# keyless-esp32.net
KiCad netlist of a schematic drawn in EAGLE
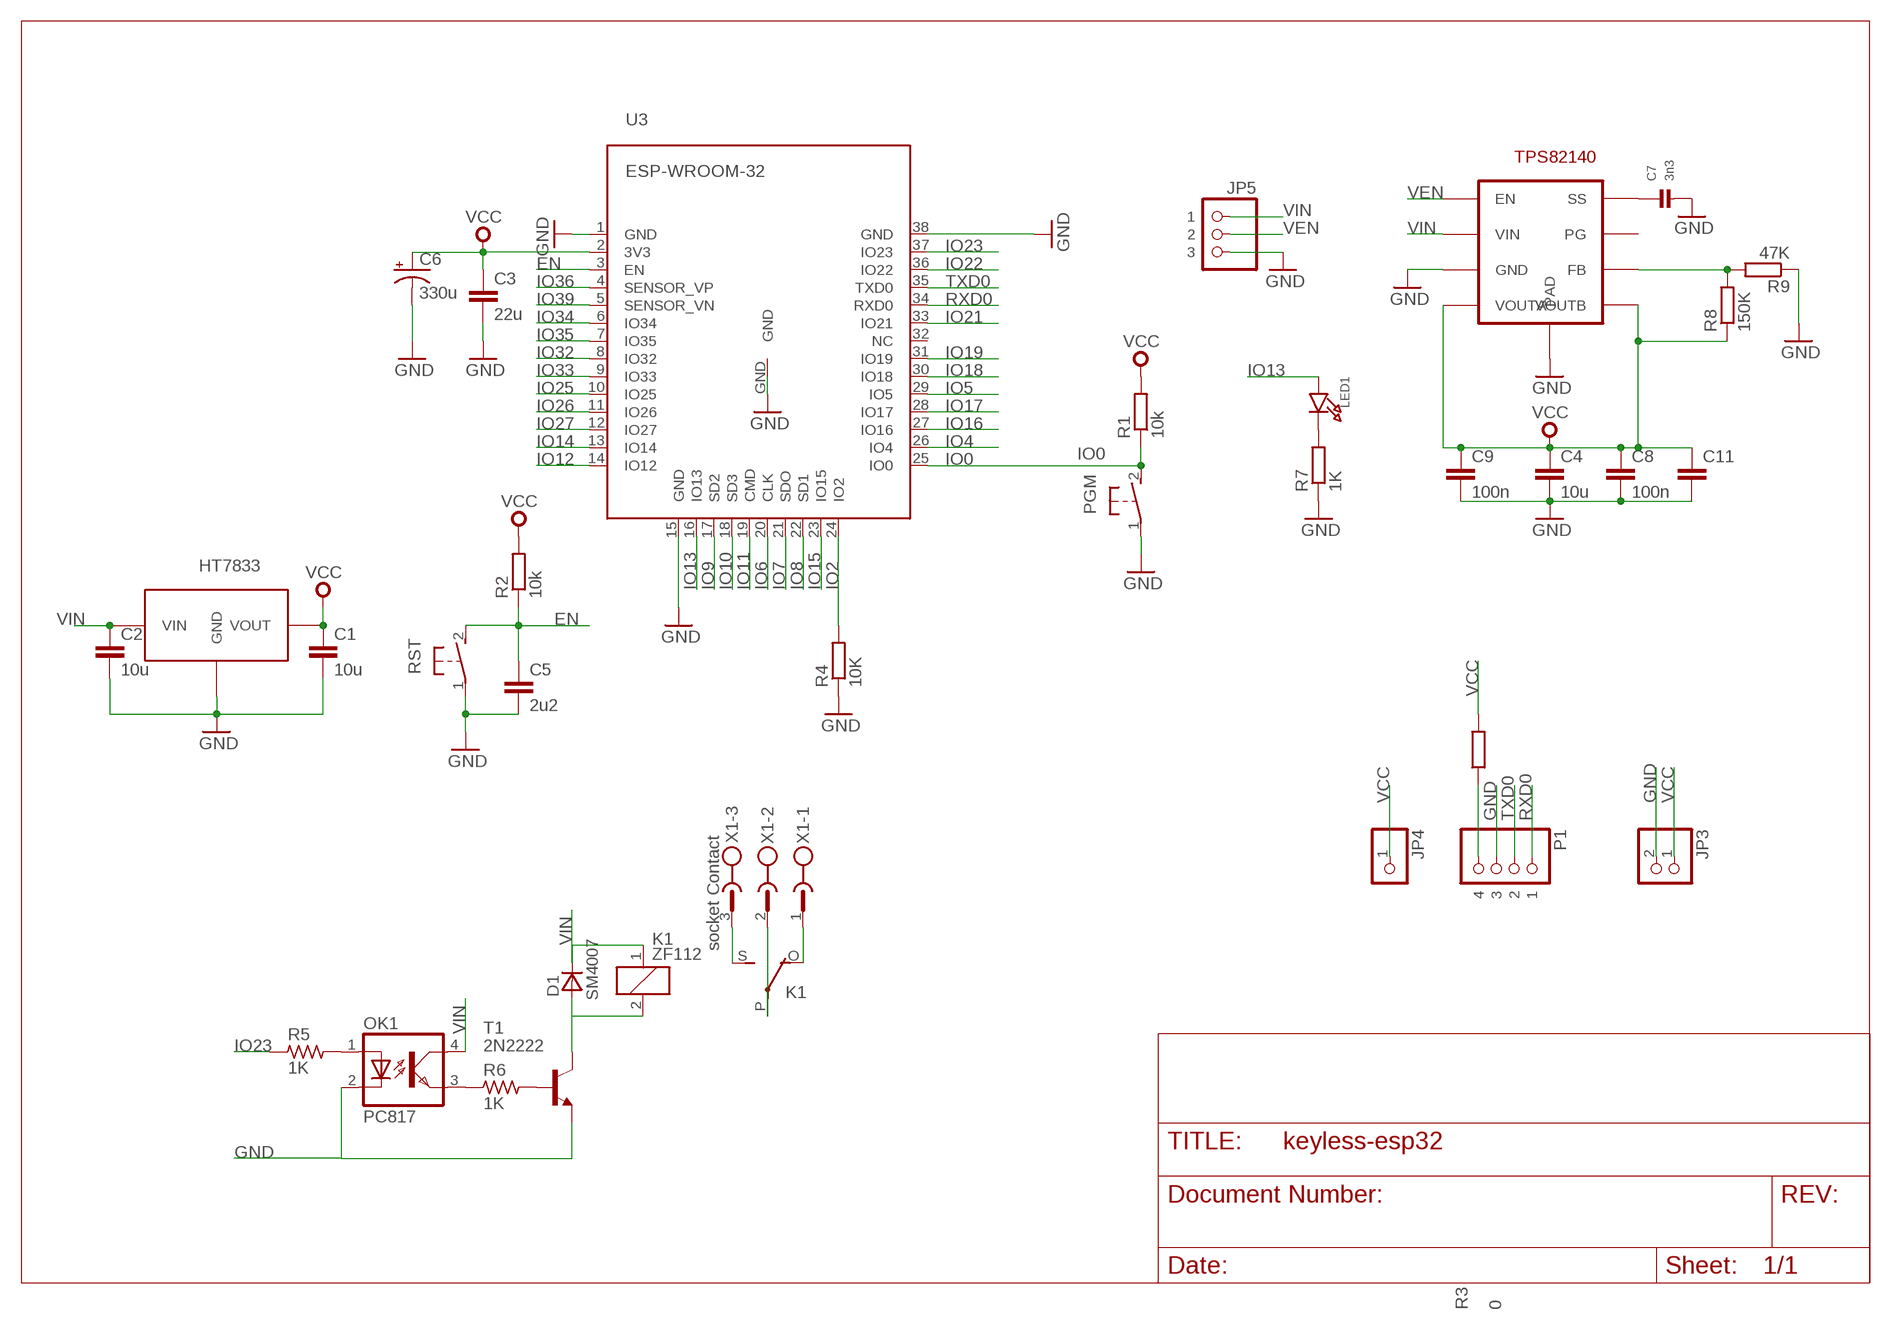
[diagram p0: schematic, sheet 1]

(export (version "E")
  (design (tool "Eeschema 10.0.6"))
  (components
    (comp (ref "C1")
      (value "10u")
      (footprint "eagle-import:C0603")
      (libsource (lib "eagle-import") (part "C-EUC0603"))
    )
    (comp (ref "C2")
      (value "10u")
      (footprint "eagle-import:C0603")
      (libsource (lib "eagle-import") (part "C-EUC0603"))
    )
    (comp (ref "C3")
      (value "22u")
      (footprint "eagle-import:0805")
      (libsource (lib "eagle-import") (part "CAP0805"))
    )
    (comp (ref "C4")
      (value "10u")
      (footprint "eagle-import:C0603")
      (libsource (lib "eagle-import") (part "C-EUC0603"))
    )
    (comp (ref "C5")
      (value "2u2")
      (footprint "eagle-import:C0603")
      (libsource (lib "eagle-import") (part "C-EUC0603"))
    )
    (comp (ref "C6")
      (value "330u")
      (footprint "eagle-import:VISHAY_C")
      (libsource (lib "eagle-import") (part "CAP_POLSMD"))
    )
    (comp (ref "C7")
      (value "3n3")
      (footprint "eagle-import:0603")
      (libsource (lib "eagle-import") (part "CAP_CERAMIC0603"))
    )
    (comp (ref "C8")
      (value "100n")
      (footprint "eagle-import:C0603")
      (libsource (lib "eagle-import") (part "C-EUC0603"))
    )
    (comp (ref "C9")
      (value "100n")
      (footprint "eagle-import:C0603")
      (libsource (lib "eagle-import") (part "C-EUC0603"))
    )
    (comp (ref "C11")
      (value "CAPSMD")
      (footprint "eagle-import:GRM43D")
      (libsource (lib "eagle-import") (part "CAPSMD"))
    )
    (comp (ref "D1")
      (value "SM4007")
      (footprint "eagle-import:MELF-MLL41")
      (libsource (lib "eagle-import") (part "SM4007"))
    )
    (comp (ref "JP3")
      (value "HEADER-1X2ROUND")
      (footprint "eagle-import:1X02_ROUND")
      (libsource (lib "eagle-import") (part "HEADER-1X2ROUND"))
    )
    (comp (ref "JP4")
      (value "HEADER-1X1ROUND")
      (footprint "eagle-import:1X01_ROUND")
      (libsource (lib "eagle-import") (part "HEADER-1X1ROUND"))
    )
    (comp (ref "JP5")
      (value "HEADER-1X3ROUND")
      (footprint "eagle-import:1X03_ROUND")
      (libsource (lib "eagle-import") (part "HEADER-1X3ROUND"))
    )
    (comp (ref "K1")
      (value "ZF112")
      (footprint "eagle-import:ZF112")
      (libsource (lib "eagle-import") (part "ZF112"))
    )
    (comp (ref "LED1")
      (value "LED0603")
      (footprint "eagle-import:CHIPLED_0603")
      (libsource (lib "eagle-import") (part "LED0603"))
    )
    (comp (ref "OK1")
      (value "PC817")
      (footprint "eagle-import:DIL04")
      (fields (field (name "MPN") "PC817X4J000F"))
      (libsource (lib "eagle-import") (part "PC817"))
    )
    (comp (ref "P1")
      (value "HEADER-1X4ROUND")
      (footprint "eagle-import:1X04_ROUND")
      (libsource (lib "eagle-import") (part "HEADER-1X4ROUND"))
    )
    (comp (ref "PGM")
      (value "DTSM-3")
      (footprint "eagle-import:DTSM-3")
      (libsource (lib "eagle-import") (part "DTSM-3"))
    )
    (comp (ref "R1")
      (value "10k")
      (footprint "eagle-import:R0603")
      (libsource (lib "eagle-import") (part "R-EU_R0603"))
    )
    (comp (ref "R2")
      (value "10k")
      (footprint "eagle-import:R0603")
      (libsource (lib "eagle-import") (part "R-EU_R0603"))
    )
    (comp (ref "R3")
      (value "0")
      (footprint "eagle-import:R0603")
      (libsource (lib "eagle-import") (part "R-EU_R0603"))
    )
    (comp (ref "R4")
      (value "10K")
      (footprint "eagle-import:R0603")
      (libsource (lib "eagle-import") (part "R-EU_R0603"))
    )
    (comp (ref "R5")
      (value "1K")
      (footprint "eagle-import:R0805")
      (libsource (lib "eagle-import") (part "R_0805"))
    )
    (comp (ref "R6")
      (value "1K")
      (footprint "eagle-import:R0805")
      (libsource (lib "eagle-import") (part "R_0805"))
    )
    (comp (ref "R7")
      (value "1K")
      (footprint "eagle-import:R0603")
      (libsource (lib "eagle-import") (part "R-EU_R0603"))
    )
    (comp (ref "R8")
      (value "150K")
      (footprint "eagle-import:R0603")
      (libsource (lib "eagle-import") (part "R-EU_R0603"))
    )
    (comp (ref "R9")
      (value "47K")
      (footprint "eagle-import:R0603")
      (libsource (lib "eagle-import") (part "R-EU_R0603"))
    )
    (comp (ref "RST")
      (value "DTSM-3")
      (footprint "eagle-import:DTSM-3")
      (libsource (lib "eagle-import") (part "DTSM-3"))
    )
    (comp (ref "T1")
      (value "2N2222")
      (footprint "eagle-import:TO18")
      (libsource (lib "eagle-import") (part "2N2222"))
    )
    (comp (ref "U$1")
      (value "HT7833")
      (footprint "eagle-import:SOT89")
      (libsource (lib "eagle-import") (part "HT7333"))
    )
    (comp (ref "U$2")
      (value "TPS82140")
      (footprint "eagle-import:TPS82140")
      (libsource (lib "eagle-import") (part "TPS82140"))
    )
    (comp (ref "U3")
      (value "ESP-WROOM-32")
      (footprint "eagle-import:ESP-WROOM-32")
      (libsource (lib "eagle-import") (part "ESP-WROOM-32"))
    )
    (comp (ref "X1")
      (value "socket Contact")
      (footprint "eagle-import:W232-3")
      (libsource (lib "eagle-import") (part "W232-3"))
    )
  )
  (nets
    (net (code "1") (name "/EN") (class "Default")
      (node (ref "C5") (pin "1") (pinfunction "1_1") (pintype "passive"))
      (node (ref "R2") (pin "1") (pinfunction "1_1") (pintype "passive"))
      (node (ref "RST") (pin "2") (pinfunction "2_2") (pintype "passive"))
      (node (ref "U3") (pin "3") (pinfunction "EN_3") (pintype "bidirectional"))
    )
    (net (code "2") (name "/IO0") (class "Default")
      (node (ref "PGM") (pin "2") (pinfunction "2_2") (pintype "passive"))
      (node (ref "R1") (pin "1") (pinfunction "1_1") (pintype "passive"))
      (node (ref "U3") (pin "25") (pinfunction "IO0_25") (pintype "bidirectional"))
    )
    (net (code "3") (name "/IO2") (class "Default")
      (node (ref "R4") (pin "2") (pinfunction "2_2") (pintype "passive"))
      (node (ref "U3") (pin "24") (pinfunction "IO2_24") (pintype "bidirectional"))
    )
    (net (code "4") (name "/IO4") (class "Default")
      (node (ref "U3") (pin "26") (pinfunction "IO4_26") (pintype "bidirectional"))
    )
    (net (code "5") (name "/IO5") (class "Default")
      (node (ref "U3") (pin "29") (pinfunction "IO5_29") (pintype "bidirectional"))
    )
    (net (code "6") (name "/IO6") (class "Default")
      (node (ref "U3") (pin "20") (pinfunction "CLK_20") (pintype "bidirectional"))
    )
    (net (code "7") (name "/IO7") (class "Default")
      (node (ref "U3") (pin "21") (pinfunction "SDO_21") (pintype "bidirectional"))
    )
    (net (code "8") (name "/IO8") (class "Default")
      (node (ref "U3") (pin "22") (pinfunction "SD1_22") (pintype "bidirectional"))
    )
    (net (code "9") (name "/IO9") (class "Default")
      (node (ref "U3") (pin "17") (pinfunction "SD2_17") (pintype "bidirectional"))
    )
    (net (code "10") (name "/IO10") (class "Default")
      (node (ref "U3") (pin "18") (pinfunction "SD3_18") (pintype "bidirectional"))
    )
    (net (code "11") (name "/IO11") (class "Default")
      (node (ref "U3") (pin "19") (pinfunction "CMD_19") (pintype "bidirectional"))
    )
    (net (code "12") (name "/IO12") (class "Default")
      (node (ref "U3") (pin "14") (pinfunction "IO12_14") (pintype "bidirectional"))
    )
    (net (code "13") (name "/IO13") (class "Default")
      (node (ref "LED1") (pin "A") (pinfunction "A_A") (pintype "passive"))
      (node (ref "U3") (pin "16") (pinfunction "IO13_16") (pintype "bidirectional"))
    )
    (net (code "14") (name "/IO14") (class "Default")
      (node (ref "U3") (pin "13") (pinfunction "IO14_13") (pintype "bidirectional"))
    )
    (net (code "15") (name "/IO15") (class "Default")
      (node (ref "U3") (pin "23") (pinfunction "IO15_23") (pintype "bidirectional"))
    )
    (net (code "16") (name "/IO16") (class "Default")
      (node (ref "U3") (pin "27") (pinfunction "IO16_27") (pintype "bidirectional"))
    )
    (net (code "17") (name "/IO17") (class "Default")
      (node (ref "U3") (pin "28") (pinfunction "IO17_28") (pintype "bidirectional"))
    )
    (net (code "18") (name "/IO18") (class "Default")
      (node (ref "U3") (pin "30") (pinfunction "IO18_30") (pintype "bidirectional"))
    )
    (net (code "19") (name "/IO19") (class "Default")
      (node (ref "U3") (pin "31") (pinfunction "IO19_31") (pintype "bidirectional"))
    )
    (net (code "20") (name "/IO21") (class "Default")
      (node (ref "U3") (pin "33") (pinfunction "IO21_33") (pintype "bidirectional"))
    )
    (net (code "21") (name "/IO22") (class "Default")
      (node (ref "U3") (pin "36") (pinfunction "IO22_36") (pintype "bidirectional"))
    )
    (net (code "22") (name "/IO23") (class "Default")
      (node (ref "R5") (pin "1") (pinfunction "1_1") (pintype "passive"))
      (node (ref "U3") (pin "37") (pinfunction "IO23_37") (pintype "bidirectional"))
    )
    (net (code "23") (name "/IO25") (class "Default")
      (node (ref "U3") (pin "10") (pinfunction "IO25_10") (pintype "bidirectional"))
    )
    (net (code "24") (name "/IO26") (class "Default")
      (node (ref "U3") (pin "11") (pinfunction "IO26_11") (pintype "bidirectional"))
    )
    (net (code "25") (name "/IO27") (class "Default")
      (node (ref "U3") (pin "12") (pinfunction "IO27_12") (pintype "bidirectional"))
    )
    (net (code "26") (name "/IO32") (class "Default")
      (node (ref "U3") (pin "8") (pinfunction "IO32_8") (pintype "bidirectional"))
    )
    (net (code "27") (name "/IO33") (class "Default")
      (node (ref "U3") (pin "9") (pinfunction "IO33_9") (pintype "bidirectional"))
    )
    (net (code "28") (name "/IO34") (class "Default")
      (node (ref "U3") (pin "6") (pinfunction "IO34_6") (pintype "bidirectional"))
    )
    (net (code "29") (name "/IO35") (class "Default")
      (node (ref "U3") (pin "7") (pinfunction "IO35_7") (pintype "bidirectional"))
    )
    (net (code "30") (name "/IO36") (class "Default")
      (node (ref "U3") (pin "4") (pinfunction "SENSOR_VP_4") (pintype "bidirectional"))
    )
    (net (code "31") (name "/IO39") (class "Default")
      (node (ref "U3") (pin "5") (pinfunction "SENSOR_VN_5") (pintype "bidirectional"))
    )
    (net (code "32") (name "/RXD0") (class "Default")
      (node (ref "P1") (pin "1") (pinfunction "1_1") (pintype "passive"))
      (node (ref "U3") (pin "34") (pinfunction "RXD0_34") (pintype "bidirectional"))
    )
    (net (code "33") (name "/TXD0") (class "Default")
      (node (ref "P1") (pin "2") (pinfunction "2_2") (pintype "passive"))
      (node (ref "U3") (pin "35") (pinfunction "TXD0_35") (pintype "bidirectional"))
    )
    (net (code "34") (name "/VEN") (class "Default")
      (node (ref "JP5") (pin "2") (pinfunction "2_2") (pintype "passive"))
      (node (ref "U$2") (pin "P$1") (pinfunction "EN_P$1") (pintype "bidirectional"))
    )
    (net (code "35") (name "/VIN") (class "Default")
      (node (ref "C2") (pin "1") (pinfunction "1_1") (pintype "passive"))
      (node (ref "D1") (pin "C") (pinfunction "C_C") (pintype "passive"))
      (node (ref "JP5") (pin "1") (pinfunction "1_1") (pintype "passive"))
      (node (ref "K1") (pin "1") (pinfunction "1_1") (pintype "passive"))
      (node (ref "OK1") (pin "4") (pinfunction "COL_4") (pintype "passive"))
      (node (ref "U$1") (pin "VIN") (pinfunction "VIN_VIN") (pintype "bidirectional"))
      (node (ref "U$2") (pin "P$2") (pinfunction "VIN_P$2") (pintype "bidirectional"))
    )
    (net (code "36") (name "GND") (class "Default")
      (node (ref "C1") (pin "2") (pinfunction "2_2") (pintype "passive"))
      (node (ref "C11") (pin "C") (pinfunction "2_C") (pintype "passive"))
      (node (ref "C2") (pin "2") (pinfunction "2_2") (pintype "passive"))
      (node (ref "C3") (pin "2") (pinfunction "2_2") (pintype "passive"))
      (node (ref "C4") (pin "2") (pinfunction "2_2") (pintype "passive"))
      (node (ref "C5") (pin "2") (pinfunction "2_2") (pintype "passive"))
      (node (ref "C6") (pin "-") (pinfunction "-_-") (pintype "passive"))
      (node (ref "C7") (pin "2") (pinfunction "P$2_2") (pintype "passive"))
      (node (ref "C8") (pin "2") (pinfunction "2_2") (pintype "passive"))
      (node (ref "C9") (pin "2") (pinfunction "2_2") (pintype "passive"))
      (node (ref "JP3") (pin "2") (pinfunction "2_2") (pintype "passive"))
      (node (ref "JP5") (pin "3") (pinfunction "3_3") (pintype "passive"))
      (node (ref "OK1") (pin "2") (pinfunction "C_2") (pintype "passive"))
      (node (ref "P1") (pin "3") (pinfunction "3_3") (pintype "passive"))
      (node (ref "PGM") (pin "1") (pinfunction "1_1") (pintype "passive"))
      (node (ref "R4") (pin "1") (pinfunction "1_1") (pintype "passive"))
      (node (ref "R7") (pin "1") (pinfunction "1_1") (pintype "passive"))
      (node (ref "R9") (pin "1") (pinfunction "1_1") (pintype "passive"))
      (node (ref "RST") (pin "1") (pinfunction "1_1") (pintype "passive"))
      (node (ref "T1") (pin "1") (pinfunction "E_1") (pintype "passive"))
      (node (ref "U$1") (pin "GND") (pinfunction "GND_GND") (pintype "bidirectional"))
      (node (ref "U$2") (pin "P$3") (pinfunction "GND_P$3") (pintype "bidirectional"))
      (node (ref "U$2") (pin "P$9") (pinfunction "PAD_P$9") (pintype "bidirectional"))
      (node (ref "U3") (pin "1") (pinfunction "GND_1") (pintype "bidirectional"))
      (node (ref "U3") (pin "15") (pinfunction "GND_15") (pintype "bidirectional"))
      (node (ref "U3") (pin "38") (pinfunction "GND_38") (pintype "bidirectional"))
      (node (ref "U3") (pin "GND") (pinfunction "GND_GND") (pintype "bidirectional"))
    )
    (net (code "37") (name "Net-(C7-P$1)") (class "Default")
      (node (ref "C7") (pin "1") (pinfunction "P$1_1") (pintype "passive"))
      (node (ref "U$2") (pin "P$8") (pinfunction "SS_P$8") (pintype "bidirectional"))
    )
    (net (code "38") (name "Net-(LED1-PadC)") (class "Default")
      (node (ref "LED1") (pin "C") (pinfunction "C_C") (pintype "passive"))
      (node (ref "R7") (pin "2") (pinfunction "2_2") (pintype "passive"))
    )
    (net (code "39") (name "Net-(OK1-A)") (class "Default")
      (node (ref "OK1") (pin "1") (pinfunction "A_1") (pintype "passive"))
      (node (ref "R5") (pin "2") (pinfunction "2_2") (pintype "passive"))
    )
    (net (code "40") (name "Net-(OK1-EMIT)") (class "Default")
      (node (ref "OK1") (pin "3") (pinfunction "EMIT_3") (pintype "passive"))
      (node (ref "R6") (pin "1") (pinfunction "1_1") (pintype "passive"))
    )
    (net (code "41") (name "Net-(P1-Pad4)") (class "Default")
      (node (ref "P1") (pin "4") (pinfunction "4_4") (pintype "passive"))
      (node (ref "R3") (pin "1") (pinfunction "1_1") (pintype "passive"))
    )
    (net (code "42") (name "Net-(T1-B)") (class "Default")
      (node (ref "R6") (pin "2") (pinfunction "2_2") (pintype "passive"))
      (node (ref "T1") (pin "2") (pinfunction "B_2") (pintype "passive"))
    )
    (net (code "43") (name "Net-(T1-C)") (class "Default")
      (node (ref "D1") (pin "A") (pinfunction "A_A") (pintype "passive"))
      (node (ref "K1") (pin "2") (pinfunction "2_2") (pintype "passive"))
      (node (ref "T1") (pin "3") (pinfunction "C_3") (pintype "passive"))
    )
    (net (code "44") (name "Net-(U$2-FB)") (class "Default")
      (node (ref "R8") (pin "2") (pinfunction "2_2") (pintype "passive"))
      (node (ref "R9") (pin "2") (pinfunction "2_2") (pintype "passive"))
      (node (ref "U$2") (pin "P$6") (pinfunction "FB_P$6") (pintype "bidirectional"))
    )
    (net (code "45") (name "Net-(X1A-SK)") (class "Default")
      (node (ref "K1") (pin "O") (pinfunction "O_O") (pintype "passive"))
      (node (ref "X1") (pin "1") (pinfunction "SK_1") (pintype "passive"))
    )
    (net (code "46") (name "Net-(X1B-SK)") (class "Default")
      (node (ref "K1") (pin "P") (pinfunction "P_P") (pintype "passive"))
      (node (ref "X1") (pin "2") (pinfunction "SK_2") (pintype "passive"))
    )
    (net (code "47") (name "Net-(X1C-SK)") (class "Default")
      (node (ref "K1") (pin "S") (pinfunction "S_S") (pintype "passive"))
      (node (ref "X1") (pin "3") (pinfunction "SK_3") (pintype "passive"))
    )
    (net (code "48") (name "VCC") (class "Default")
      (node (ref "C1") (pin "1") (pinfunction "1_1") (pintype "passive"))
      (node (ref "C11") (pin "A") (pinfunction "1_A") (pintype "passive"))
      (node (ref "C3") (pin "1") (pinfunction "1_1") (pintype "passive"))
      (node (ref "C4") (pin "1") (pinfunction "1_1") (pintype "passive"))
      (node (ref "C6") (pin "+") (pinfunction "+_+") (pintype "passive"))
      (node (ref "C8") (pin "1") (pinfunction "1_1") (pintype "passive"))
      (node (ref "C9") (pin "1") (pinfunction "1_1") (pintype "passive"))
      (node (ref "JP3") (pin "1") (pinfunction "1_1") (pintype "passive"))
      (node (ref "JP4") (pin "1") (pinfunction "1_1") (pintype "passive"))
      (node (ref "R1") (pin "2") (pinfunction "2_2") (pintype "passive"))
      (node (ref "R2") (pin "2") (pinfunction "2_2") (pintype "passive"))
      (node (ref "R3") (pin "2") (pinfunction "2_2") (pintype "passive"))
      (node (ref "R8") (pin "1") (pinfunction "1_1") (pintype "passive"))
      (node (ref "U$1") (pin "VOUT") (pinfunction "VOUT_VOUT") (pintype "bidirectional"))
      (node (ref "U$2") (pin "P$4") (pinfunction "VOUTA_P$4") (pintype "bidirectional"))
      (node (ref "U$2") (pin "P$5") (pinfunction "VOUTB_P$5") (pintype "bidirectional"))
      (node (ref "U3") (pin "2") (pinfunction "3V3_2") (pintype "bidirectional"))
    )
    (net (code "49") (name "unconnected-(U$2-PG-PadP$7)") (class "Default")
      (node (ref "U$2") (pin "P$7") (pinfunction "PG_P$7") (pintype "bidirectional"))
    )
    (net (code "50") (name "unconnected-(U3-NC-Pad32)") (class "Default")
      (node (ref "U3") (pin "32") (pinfunction "NC_32") (pintype "bidirectional"))
    )
  )
)
